# RGB2LVDS_DS90C385A.net
KiCad netlist of a schematic drawn in Altium Designer
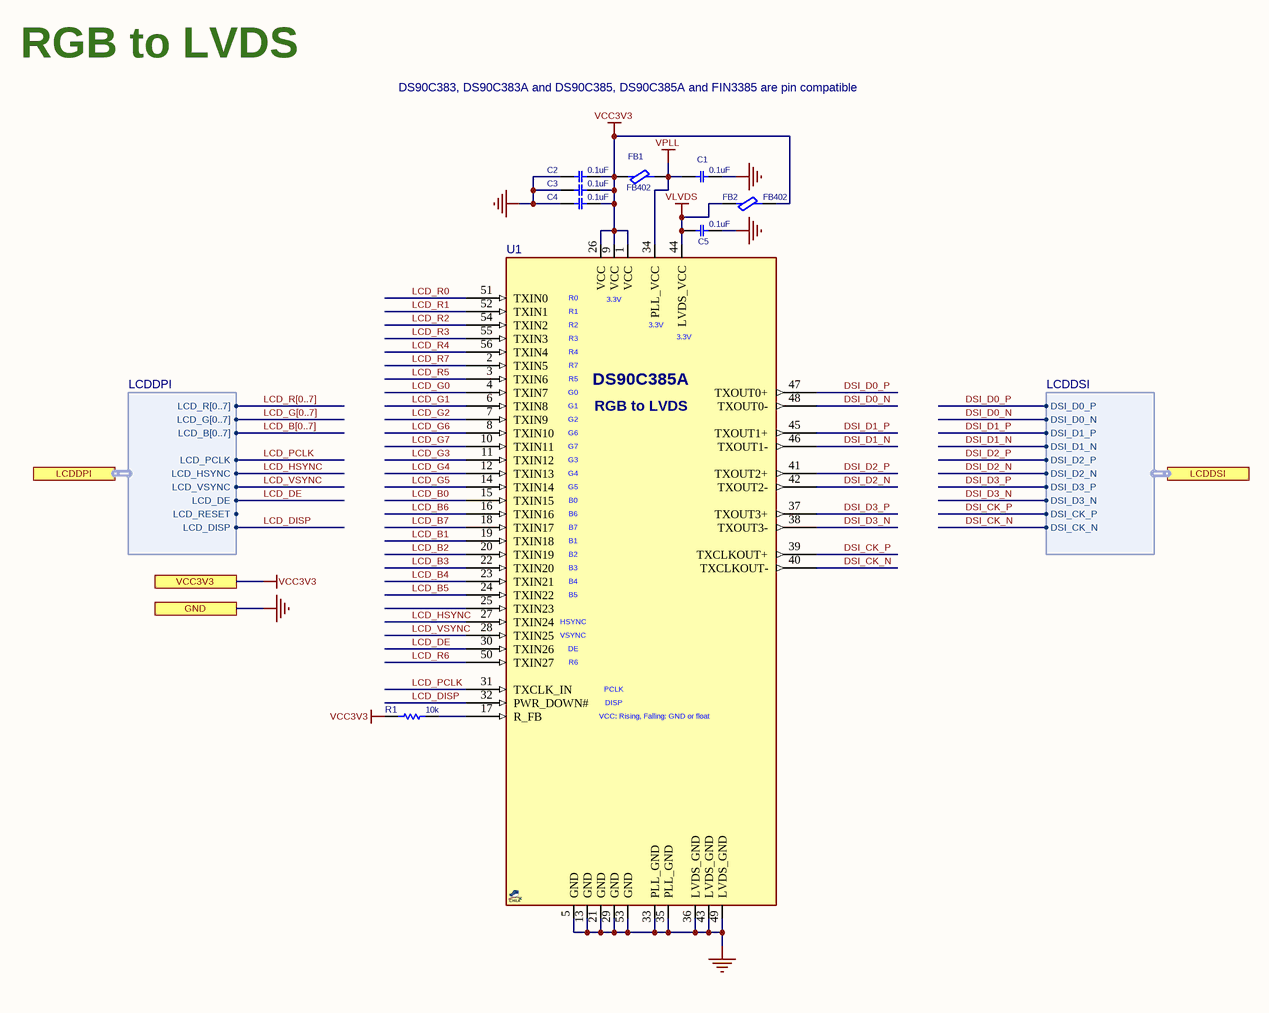
[diagram p0: RGB2LVDS_DS90C385A.SchDoc]

(export (version "E")
  (design (tool "Eeschema 10.0.6"))
  (components
    (comp (ref "C1")
      (value "0.1uF")
      (footprint "C0402")
      (description "CAP, MLCC")
      (fields (field (name "MANF_P#") "GRM155R71H104KE14D") (field (name "MANF") "Murata"))
      (libsource (lib "passive_smd") (part "CAP_SMD_MLCC"))
    )
    (comp (ref "C2")
      (value "0.1uF")
      (footprint "C0402")
      (description "CAP, MLCC")
      (fields (field (name "MANF_P#") "GRM155R71H104KE14D") (field (name "MANF") "Murata"))
      (libsource (lib "passive_smd") (part "CAP_SMD_MLCC"))
    )
    (comp (ref "C3")
      (value "0.1uF")
      (footprint "C0402")
      (description "CAP, MLCC")
      (fields (field (name "MANF_P#") "GRM155R71H104KE14D") (field (name "MANF") "Murata"))
      (libsource (lib "passive_smd") (part "CAP_SMD_MLCC"))
    )
    (comp (ref "C4")
      (value "0.1uF")
      (footprint "C0402")
      (description "CAP, MLCC")
      (fields (field (name "MANF_P#") "GRM155R71H104KE14D") (field (name "MANF") "Murata"))
      (libsource (lib "passive_smd") (part "CAP_SMD_MLCC"))
    )
    (comp (ref "C5")
      (value "0.1uF")
      (footprint "C0402")
      (description "CAP, MLCC")
      (fields (field (name "MANF_P#") "GRM155R71H104KE14D") (field (name "MANF") "Murata"))
      (libsource (lib "passive_smd") (part "CAP_SMD_MLCC"))
    )
    (comp (ref "FB1")
      (value "FB402")
      (footprint "L0402")
      (description "FERRITE_Bead, 0402, 0.5A, 200mOhm, 120@100MHz")
      (fields (field (name "MANF") "MURATA") (field (name "MANF_P#") "BLM15AG121SN1D"))
      (libsource (lib "emi_filter") (part "FBEAD_SMD_BLM15PD121"))
    )
    (comp (ref "FB2")
      (value "FB402")
      (footprint "L0402")
      (description "FERRITE_Bead, 0402, 0.5A, 200mOhm, 120@100MHz")
      (fields (field (name "MANF") "MURATA") (field (name "MANF_P#") "BLM15AG121SN1D"))
      (libsource (lib "emi_filter") (part "FBEAD_SMD_BLM15PD121"))
    )
    (comp (ref "R1")
      (value "10k")
      (footprint "R0402")
      (description "RESISTOR, SMD")
      (libsource (lib "passive_res_smd") (part "RES_SMD"))
    )
    (comp (ref "U1")
      (value "DS90C385A")
      (footprint "SOG50_56")
      (description "RGB receiver, LVDS transmitter, 87.5MHz, 24-bit video inputs")
      (fields (field (name "MANF") "Texas Instruments") (field (name "MANF_P#") "DS90C385AMT, DS90C385AMTX"))
      (libsource (lib "display_interface_bridge") (part "DS90C385A_TSSOP56"))
    )
  )
  (nets
    (net (code "3") (name "/DSI_CK_N") (class "Default")
      (node (ref "U1") (pin "40") (pinfunction "TXCLKOUT-_40") (pintype "output"))
    )
    (net (code "4") (name "/DSI_CK_P") (class "Default")
      (node (ref "U1") (pin "39") (pinfunction "TXCLKOUT+_39") (pintype "output"))
    )
    (net (code "5") (name "/DSI_D0_N") (class "Default")
      (node (ref "U1") (pin "48") (pinfunction "TXOUT0-_48") (pintype "output"))
    )
    (net (code "6") (name "/DSI_D0_P") (class "Default")
      (node (ref "U1") (pin "47") (pinfunction "TXOUT0+_47") (pintype "output"))
    )
    (net (code "7") (name "/DSI_D1_N") (class "Default")
      (node (ref "U1") (pin "46") (pinfunction "TXOUT1-_46") (pintype "output"))
    )
    (net (code "8") (name "/DSI_D1_P") (class "Default")
      (node (ref "U1") (pin "45") (pinfunction "TXOUT1+_45") (pintype "output"))
    )
    (net (code "9") (name "/DSI_D2_N") (class "Default")
      (node (ref "U1") (pin "42") (pinfunction "TXOUT2-_42") (pintype "output"))
    )
    (net (code "10") (name "/DSI_D2_P") (class "Default")
      (node (ref "U1") (pin "41") (pinfunction "TXOUT2+_41") (pintype "output"))
    )
    (net (code "11") (name "/DSI_D3_N") (class "Default")
      (node (ref "U1") (pin "38") (pinfunction "TXOUT3-_38") (pintype "output"))
    )
    (net (code "12") (name "/DSI_D3_P") (class "Default")
      (node (ref "U1") (pin "37") (pinfunction "TXOUT3+_37") (pintype "output"))
    )
    (net (code "14") (name "/LCD_B0") (class "Default")
      (node (ref "U1") (pin "15") (pinfunction "TXIN15_15") (pintype "input"))
    )
    (net (code "15") (name "/LCD_B1") (class "Default")
      (node (ref "U1") (pin "19") (pinfunction "TXIN18_19") (pintype "input"))
    )
    (net (code "16") (name "/LCD_B2") (class "Default")
      (node (ref "U1") (pin "20") (pinfunction "TXIN19_20") (pintype "input"))
    )
    (net (code "17") (name "/LCD_B3") (class "Default")
      (node (ref "U1") (pin "22") (pinfunction "TXIN20_22") (pintype "input"))
    )
    (net (code "18") (name "/LCD_B4") (class "Default")
      (node (ref "U1") (pin "23") (pinfunction "TXIN21_23") (pintype "input"))
    )
    (net (code "19") (name "/LCD_B5") (class "Default")
      (node (ref "U1") (pin "24") (pinfunction "TXIN22_24") (pintype "input"))
    )
    (net (code "20") (name "/LCD_B6") (class "Default")
      (node (ref "U1") (pin "16") (pinfunction "TXIN16_16") (pintype "input"))
    )
    (net (code "21") (name "/LCD_B7") (class "Default")
      (node (ref "U1") (pin "18") (pinfunction "TXIN17_18") (pintype "input"))
    )
    (net (code "22") (name "/LCD_DE") (class "Default")
      (node (ref "U1") (pin "30") (pinfunction "TXIN26_30") (pintype "input"))
    )
    (net (code "23") (name "/LCD_DISP") (class "Default")
      (node (ref "U1") (pin "32") (pinfunction "PWR_DOWN#_32") (pintype "input"))
    )
    (net (code "24") (name "/LCD_G0") (class "Default")
      (node (ref "U1") (pin "4") (pinfunction "TXIN7_4") (pintype "input"))
    )
    (net (code "25") (name "/LCD_G1") (class "Default")
      (node (ref "U1") (pin "6") (pinfunction "TXIN8_6") (pintype "input"))
    )
    (net (code "26") (name "/LCD_G2") (class "Default")
      (node (ref "U1") (pin "7") (pinfunction "TXIN9_7") (pintype "input"))
    )
    (net (code "27") (name "/LCD_G3") (class "Default")
      (node (ref "U1") (pin "11") (pinfunction "TXIN12_11") (pintype "input"))
    )
    (net (code "28") (name "/LCD_G4") (class "Default")
      (node (ref "U1") (pin "12") (pinfunction "TXIN13_12") (pintype "input"))
    )
    (net (code "29") (name "/LCD_G5") (class "Default")
      (node (ref "U1") (pin "14") (pinfunction "TXIN14_14") (pintype "input"))
    )
    (net (code "30") (name "/LCD_G6") (class "Default")
      (node (ref "U1") (pin "8") (pinfunction "TXIN10_8") (pintype "input"))
    )
    (net (code "31") (name "/LCD_G7") (class "Default")
      (node (ref "U1") (pin "10") (pinfunction "TXIN11_10") (pintype "input"))
    )
    (net (code "33") (name "/LCD_HSYNC") (class "Default")
      (node (ref "U1") (pin "27") (pinfunction "TXIN24_27") (pintype "input"))
    )
    (net (code "34") (name "/LCD_PCLK") (class "Default")
      (node (ref "U1") (pin "31") (pinfunction "TXCLK_IN_31") (pintype "input"))
    )
    (net (code "35") (name "/LCD_R0") (class "Default")
      (node (ref "U1") (pin "51") (pinfunction "TXIN0_51") (pintype "input"))
    )
    (net (code "36") (name "/LCD_R1") (class "Default")
      (node (ref "U1") (pin "52") (pinfunction "TXIN1_52") (pintype "input"))
    )
    (net (code "37") (name "/LCD_R2") (class "Default")
      (node (ref "U1") (pin "54") (pinfunction "TXIN2_54") (pintype "input"))
    )
    (net (code "38") (name "/LCD_R3") (class "Default")
      (node (ref "U1") (pin "55") (pinfunction "TXIN3_55") (pintype "input"))
    )
    (net (code "39") (name "/LCD_R4") (class "Default")
      (node (ref "U1") (pin "56") (pinfunction "TXIN4_56") (pintype "input"))
    )
    (net (code "40") (name "/LCD_R5") (class "Default")
      (node (ref "U1") (pin "3") (pinfunction "TXIN6_3") (pintype "input"))
    )
    (net (code "41") (name "/LCD_R6") (class "Default")
      (node (ref "U1") (pin "50") (pinfunction "TXIN27_50") (pintype "input"))
    )
    (net (code "42") (name "/LCD_R7") (class "Default")
      (node (ref "U1") (pin "2") (pinfunction "TXIN5_2") (pintype "input"))
    )
    (net (code "44") (name "/LCD_VSYNC") (class "Default")
      (node (ref "U1") (pin "28") (pinfunction "TXIN25_28") (pintype "input"))
    )
    (net (code "47") (name "GND") (class "Default")
      (node (ref "C1") (pin "1") (pinfunction "1_1") (pintype "passive"))
      (node (ref "C2") (pin "2") (pinfunction "2_2") (pintype "passive"))
      (node (ref "C3") (pin "2") (pinfunction "2_2") (pintype "passive"))
      (node (ref "C4") (pin "2") (pinfunction "2_2") (pintype "passive"))
      (node (ref "C5") (pin "1") (pinfunction "1_1") (pintype "passive"))
      (node (ref "U1") (pin "13") (pinfunction "GND_13") (pintype "power_in"))
      (node (ref "U1") (pin "21") (pinfunction "GND_21") (pintype "power_in"))
      (node (ref "U1") (pin "29") (pinfunction "GND_29") (pintype "power_in"))
      (node (ref "U1") (pin "33") (pinfunction "PLL_GND_33") (pintype "power_in"))
      (node (ref "U1") (pin "35") (pinfunction "PLL_GND_35") (pintype "power_in"))
      (node (ref "U1") (pin "36") (pinfunction "LVDS_GND_36") (pintype "power_in"))
      (node (ref "U1") (pin "43") (pinfunction "LVDS_GND_43") (pintype "power_in"))
      (node (ref "U1") (pin "49") (pinfunction "LVDS_GND_49") (pintype "power_in"))
      (node (ref "U1") (pin "5") (pinfunction "GND_5") (pintype "power_in"))
      (node (ref "U1") (pin "53") (pinfunction "GND_53") (pintype "power_in"))
    )
    (net (code "48") (name "Net-(U1-R_FB)") (class "Default")
      (node (ref "R1") (pin "2") (pinfunction "2_2") (pintype "passive"))
      (node (ref "U1") (pin "17") (pinfunction "R_FB_17") (pintype "input"))
    )
    (net (code "49") (name "VCC3V3") (class "Default")
      (node (ref "C2") (pin "1") (pinfunction "1_1") (pintype "passive"))
      (node (ref "C3") (pin "1") (pinfunction "1_1") (pintype "passive"))
      (node (ref "C4") (pin "1") (pinfunction "1_1") (pintype "passive"))
      (node (ref "FB1") (pin "1") (pinfunction "1_1") (pintype "passive"))
      (node (ref "FB2") (pin "2") (pinfunction "2_2") (pintype "passive"))
      (node (ref "R1") (pin "1") (pinfunction "1_1") (pintype "passive"))
      (node (ref "U1") (pin "1") (pinfunction "VCC_1") (pintype "power_in"))
      (node (ref "U1") (pin "26") (pinfunction "VCC_26") (pintype "power_in"))
      (node (ref "U1") (pin "9") (pinfunction "VCC_9") (pintype "power_in"))
    )
    (net (code "50") (name "VLVDS") (class "Default")
      (node (ref "C5") (pin "2") (pinfunction "2_2") (pintype "passive"))
      (node (ref "FB2") (pin "1") (pinfunction "1_1") (pintype "passive"))
      (node (ref "U1") (pin "44") (pinfunction "LVDS_VCC_44") (pintype "power_in"))
    )
    (net (code "51") (name "VPLL") (class "Default")
      (node (ref "C1") (pin "2") (pinfunction "2_2") (pintype "passive"))
      (node (ref "FB1") (pin "2") (pinfunction "2_2") (pintype "passive"))
      (node (ref "U1") (pin "34") (pinfunction "PLL_VCC_34") (pintype "power_in"))
    )
    (net (code "52") (name "unconnected-(U1-TXIN23-Pad25)") (class "Default")
      (node (ref "U1") (pin "25") (pinfunction "TXIN23_25") (pintype "input"))
    )
  )
)
